# CellMonitor1.net
KiCad netlist of a schematic drawn in Altium Designer
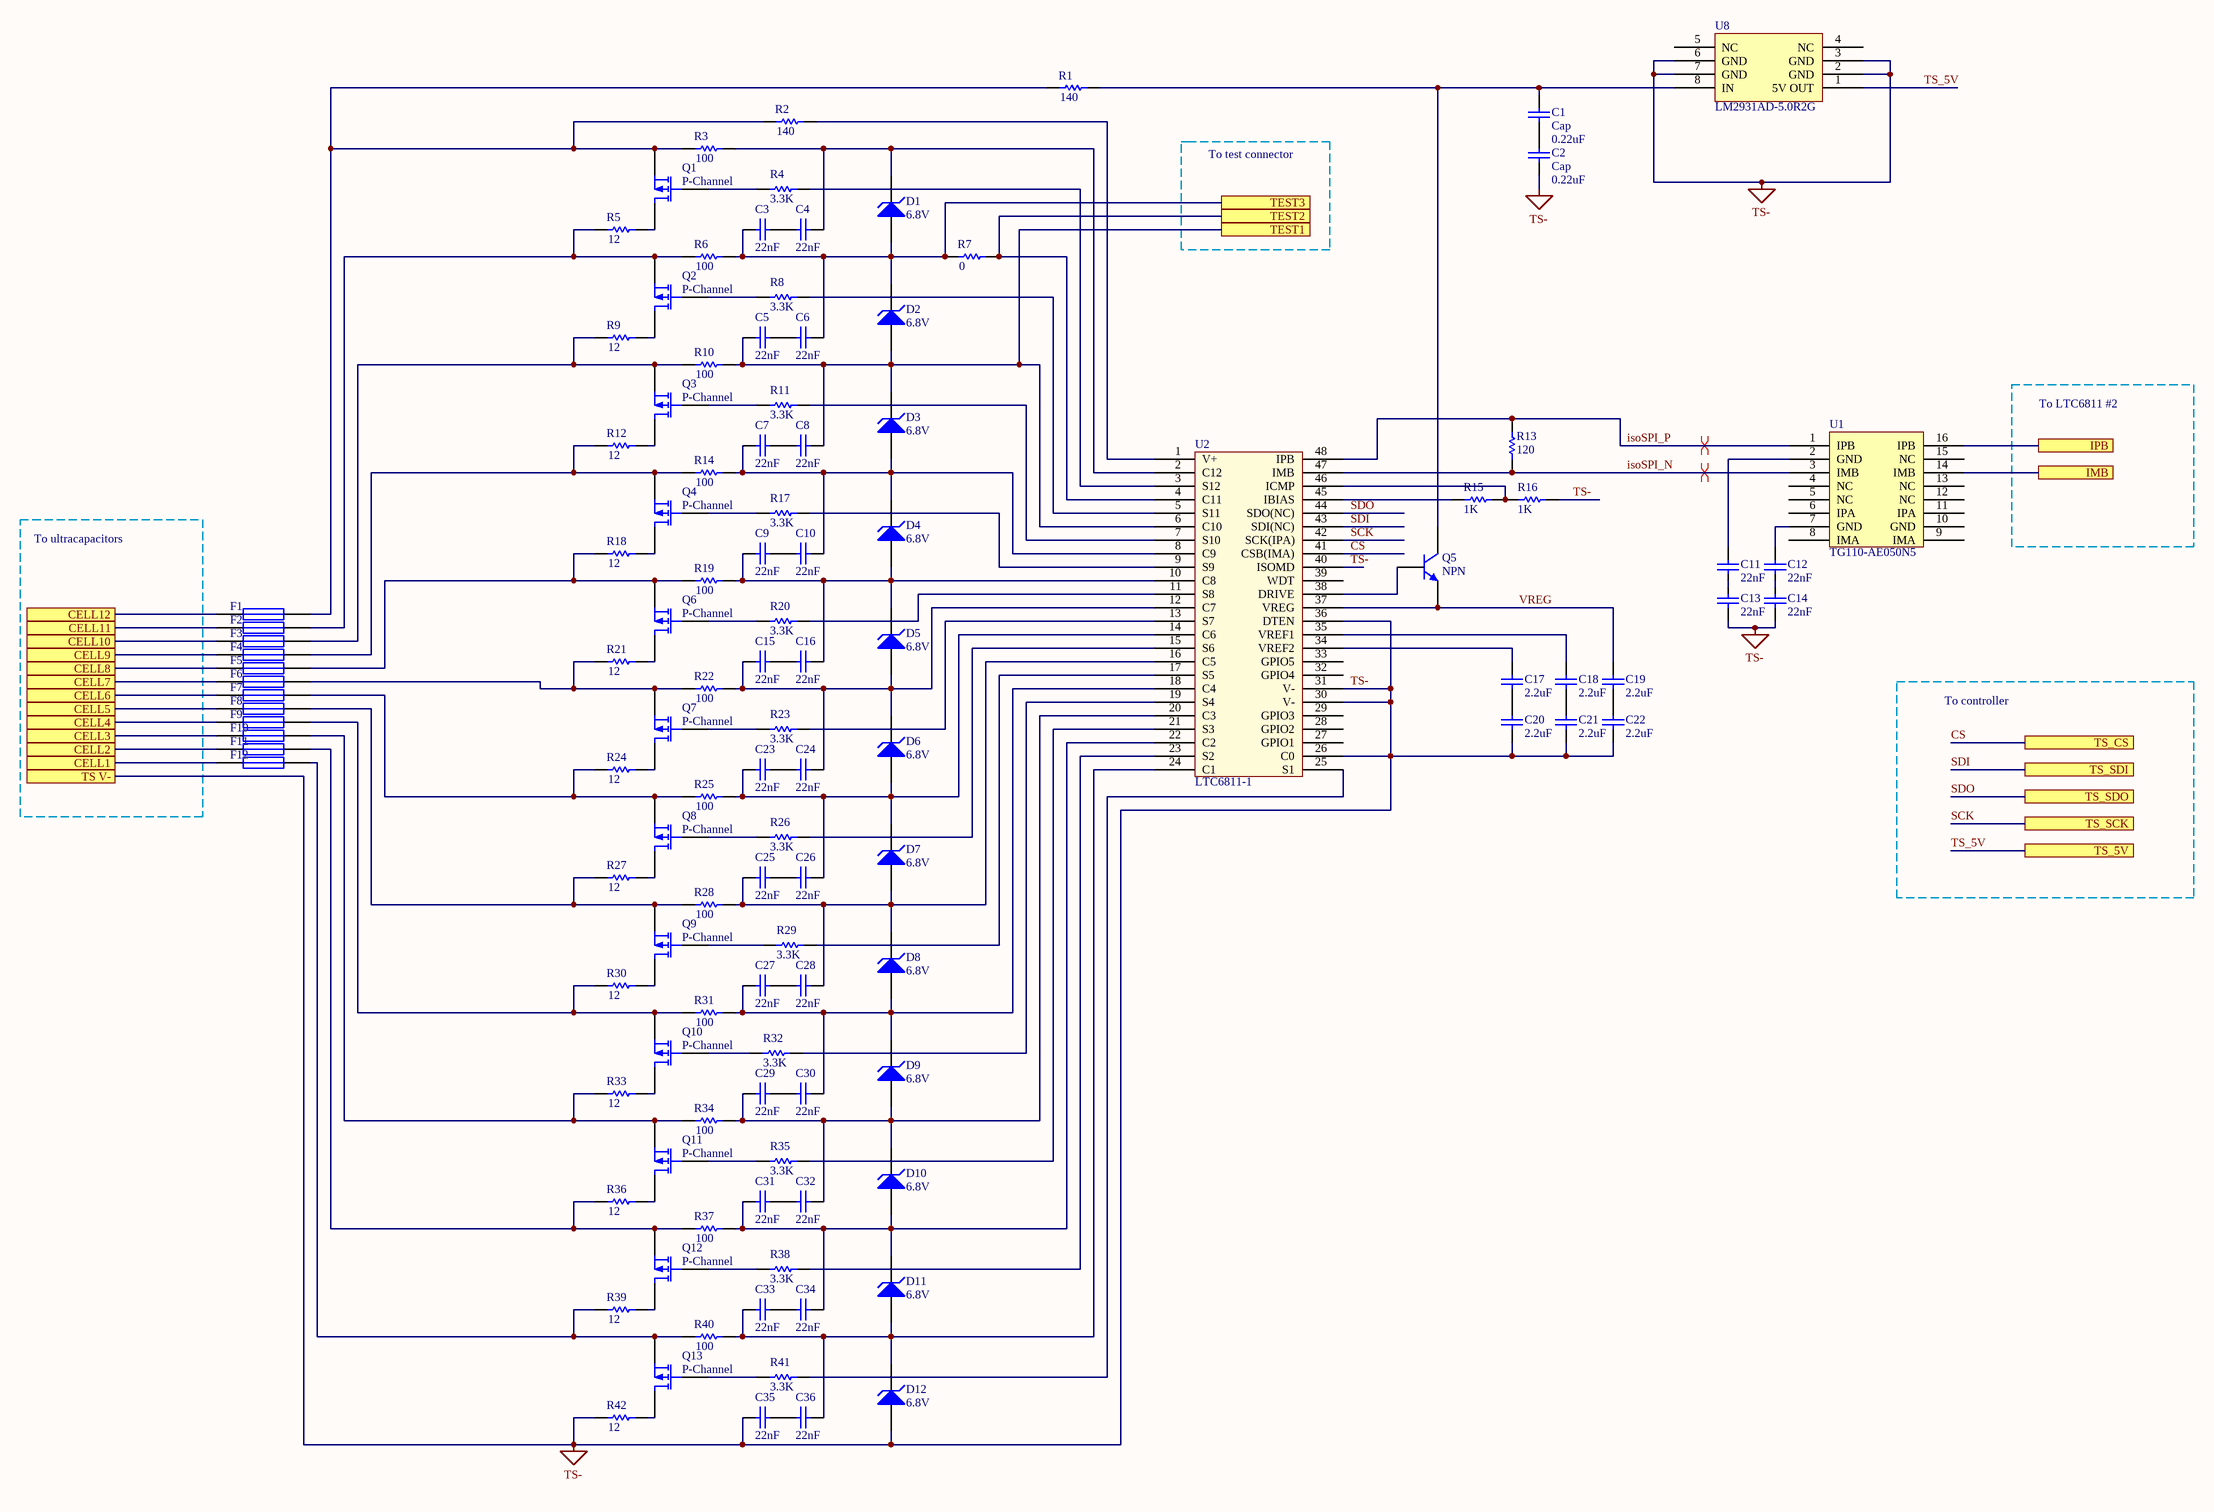
[diagram p0: CellMonitor1.SchDoc]

(export (version "E")
  (design (tool "Eeschema 10.0.6"))
  (components
    (comp (ref "C1")
      (value "Cap")
      (footprint "0603 IMPERIAL")
      (description "Capacitor")
      (fields (field (name "ALTIUM_VALUE") "0.22uF"))
      (libsource (lib "Miscellaneous Devices") (part "Cap"))
    )
    (comp (ref "C2")
      (value "Cap")
      (footprint "0603 IMPERIAL")
      (description "Capacitor")
      (fields (field (name "ALTIUM_VALUE") "0.22uF"))
      (libsource (lib "Miscellaneous Devices") (part "Cap"))
    )
    (comp (ref "C3")
      (value "22nF")
      (footprint "0603 IMPERIAL")
      (description "Capacitor")
      (fields (field (name "Comment") "Cap"))
      (libsource (lib "Miscellaneous Devices") (part "Cap"))
    )
    (comp (ref "C4")
      (value "22nF")
      (footprint "0603 IMPERIAL")
      (description "Capacitor")
      (fields (field (name "Comment") "Cap"))
      (libsource (lib "Miscellaneous Devices") (part "Cap"))
    )
    (comp (ref "C5")
      (value "22nF")
      (footprint "0603 IMPERIAL")
      (description "Capacitor")
      (fields (field (name "Comment") "Cap"))
      (libsource (lib "Miscellaneous Devices") (part "Cap"))
    )
    (comp (ref "C6")
      (value "22nF")
      (footprint "0603 IMPERIAL")
      (description "Capacitor")
      (fields (field (name "Comment") "Cap"))
      (libsource (lib "Miscellaneous Devices") (part "Cap"))
    )
    (comp (ref "C7")
      (value "22nF")
      (footprint "0603 IMPERIAL")
      (description "Capacitor")
      (fields (field (name "Comment") "Cap"))
      (libsource (lib "Miscellaneous Devices") (part "Cap"))
    )
    (comp (ref "C8")
      (value "22nF")
      (footprint "0603 IMPERIAL")
      (description "Capacitor")
      (fields (field (name "Comment") "Cap"))
      (libsource (lib "Miscellaneous Devices") (part "Cap"))
    )
    (comp (ref "C9")
      (value "22nF")
      (footprint "0603 IMPERIAL")
      (description "Capacitor")
      (fields (field (name "Comment") "Cap"))
      (libsource (lib "Miscellaneous Devices") (part "Cap"))
    )
    (comp (ref "C10")
      (value "22nF")
      (footprint "0603 IMPERIAL")
      (description "Capacitor")
      (fields (field (name "Comment") "Cap"))
      (libsource (lib "Miscellaneous Devices") (part "Cap"))
    )
    (comp (ref "C11")
      (value "22nF")
      (footprint "0603 IMPERIAL")
      (description "Capacitor")
      (fields (field (name "Comment") "Cap"))
      (libsource (lib "Miscellaneous Devices") (part "Cap"))
    )
    (comp (ref "C12")
      (value "22nF")
      (footprint "0603 IMPERIAL")
      (description "Capacitor")
      (fields (field (name "Comment") "Cap"))
      (libsource (lib "Miscellaneous Devices") (part "Cap"))
    )
    (comp (ref "C13")
      (value "22nF")
      (footprint "0603 IMPERIAL")
      (description "Capacitor")
      (fields (field (name "Comment") "Cap"))
      (libsource (lib "Miscellaneous Devices") (part "Cap"))
    )
    (comp (ref "C14")
      (value "22nF")
      (footprint "0603 IMPERIAL")
      (description "Capacitor")
      (fields (field (name "Comment") "Cap"))
      (libsource (lib "Miscellaneous Devices") (part "Cap"))
    )
    (comp (ref "C15")
      (value "22nF")
      (footprint "0603 IMPERIAL")
      (description "Capacitor")
      (fields (field (name "Comment") "Cap"))
      (libsource (lib "Miscellaneous Devices") (part "Cap"))
    )
    (comp (ref "C16")
      (value "22nF")
      (footprint "0603 IMPERIAL")
      (description "Capacitor")
      (fields (field (name "Comment") "Cap"))
      (libsource (lib "Miscellaneous Devices") (part "Cap"))
    )
    (comp (ref "C17")
      (value "2.2uF")
      (footprint "0603 IMPERIAL")
      (description "Capacitor")
      (fields (field (name "Comment") "Cap"))
      (libsource (lib "Miscellaneous Devices") (part "Cap"))
    )
    (comp (ref "C18")
      (value "2.2uF")
      (footprint "0603 IMPERIAL")
      (description "Capacitor")
      (fields (field (name "Comment") "Cap"))
      (libsource (lib "Miscellaneous Devices") (part "Cap"))
    )
    (comp (ref "C19")
      (value "2.2uF")
      (footprint "0603 IMPERIAL")
      (description "Capacitor")
      (fields (field (name "Comment") "Cap"))
      (libsource (lib "Miscellaneous Devices") (part "Cap"))
    )
    (comp (ref "C20")
      (value "2.2uF")
      (footprint "0603 IMPERIAL")
      (description "Capacitor")
      (fields (field (name "Comment") "Cap"))
      (libsource (lib "Miscellaneous Devices") (part "Cap"))
    )
    (comp (ref "C21")
      (value "2.2uF")
      (footprint "0603 IMPERIAL")
      (description "Capacitor")
      (fields (field (name "Comment") "Cap"))
      (libsource (lib "Miscellaneous Devices") (part "Cap"))
    )
    (comp (ref "C22")
      (value "2.2uF")
      (footprint "0603 IMPERIAL")
      (description "Capacitor")
      (fields (field (name "Comment") "Cap"))
      (libsource (lib "Miscellaneous Devices") (part "Cap"))
    )
    (comp (ref "C23")
      (value "22nF")
      (footprint "0603 IMPERIAL")
      (description "Capacitor")
      (fields (field (name "Comment") "Cap"))
      (libsource (lib "Miscellaneous Devices") (part "Cap"))
    )
    (comp (ref "C24")
      (value "22nF")
      (footprint "0603 IMPERIAL")
      (description "Capacitor")
      (fields (field (name "Comment") "Cap"))
      (libsource (lib "Miscellaneous Devices") (part "Cap"))
    )
    (comp (ref "C25")
      (value "22nF")
      (footprint "0603 IMPERIAL")
      (description "Capacitor")
      (fields (field (name "Comment") "Cap"))
      (libsource (lib "Miscellaneous Devices") (part "Cap"))
    )
    (comp (ref "C26")
      (value "22nF")
      (footprint "0603 IMPERIAL")
      (description "Capacitor")
      (fields (field (name "Comment") "Cap"))
      (libsource (lib "Miscellaneous Devices") (part "Cap"))
    )
    (comp (ref "C27")
      (value "22nF")
      (footprint "0603 IMPERIAL")
      (description "Capacitor")
      (fields (field (name "Comment") "Cap"))
      (libsource (lib "Miscellaneous Devices") (part "Cap"))
    )
    (comp (ref "C28")
      (value "22nF")
      (footprint "0603 IMPERIAL")
      (description "Capacitor")
      (fields (field (name "Comment") "Cap"))
      (libsource (lib "Miscellaneous Devices") (part "Cap"))
    )
    (comp (ref "C29")
      (value "22nF")
      (footprint "0603 IMPERIAL")
      (description "Capacitor")
      (fields (field (name "Comment") "Cap"))
      (libsource (lib "Miscellaneous Devices") (part "Cap"))
    )
    (comp (ref "C30")
      (value "22nF")
      (footprint "0603 IMPERIAL")
      (description "Capacitor")
      (fields (field (name "Comment") "Cap"))
      (libsource (lib "Miscellaneous Devices") (part "Cap"))
    )
    (comp (ref "C31")
      (value "22nF")
      (footprint "0603 IMPERIAL")
      (description "Capacitor")
      (fields (field (name "Comment") "Cap"))
      (libsource (lib "Miscellaneous Devices") (part "Cap"))
    )
    (comp (ref "C32")
      (value "22nF")
      (footprint "0603 IMPERIAL")
      (description "Capacitor")
      (fields (field (name "Comment") "Cap"))
      (libsource (lib "Miscellaneous Devices") (part "Cap"))
    )
    (comp (ref "C33")
      (value "22nF")
      (footprint "0603 IMPERIAL")
      (description "Capacitor")
      (fields (field (name "Comment") "Cap"))
      (libsource (lib "Miscellaneous Devices") (part "Cap"))
    )
    (comp (ref "C34")
      (value "22nF")
      (footprint "0603 IMPERIAL")
      (description "Capacitor")
      (fields (field (name "Comment") "Cap"))
      (libsource (lib "Miscellaneous Devices") (part "Cap"))
    )
    (comp (ref "C35")
      (value "22nF")
      (footprint "0603 IMPERIAL")
      (description "Capacitor")
      (fields (field (name "Comment") "Cap"))
      (libsource (lib "Miscellaneous Devices") (part "Cap"))
    )
    (comp (ref "C36")
      (value "22nF")
      (footprint "0603 IMPERIAL")
      (description "Capacitor")
      (fields (field (name "Comment") "Cap"))
      (libsource (lib "Miscellaneous Devices") (part "Cap"))
    )
    (comp (ref "D1")
      (value "6.8V")
      (footprint "SOD-323")
      (description "Zener Diode")
      (libsource (lib "Miscellaneous Devices") (part "D Zener"))
    )
    (comp (ref "D2")
      (value "6.8V")
      (footprint "SOD-323")
      (description "Zener Diode")
      (libsource (lib "Miscellaneous Devices") (part "D Zener"))
    )
    (comp (ref "D3")
      (value "6.8V")
      (footprint "SOD-323")
      (description "Zener Diode")
      (libsource (lib "Miscellaneous Devices") (part "D Zener"))
    )
    (comp (ref "D4")
      (value "6.8V")
      (footprint "SOD-323")
      (description "Zener Diode")
      (libsource (lib "Miscellaneous Devices") (part "D Zener"))
    )
    (comp (ref "D5")
      (value "6.8V")
      (footprint "SOD-323")
      (description "Zener Diode")
      (libsource (lib "Miscellaneous Devices") (part "D Zener"))
    )
    (comp (ref "D6")
      (value "6.8V")
      (footprint "SOD-323")
      (description "Zener Diode")
      (libsource (lib "Miscellaneous Devices") (part "D Zener"))
    )
    (comp (ref "D7")
      (value "6.8V")
      (footprint "SOD-323")
      (description "Zener Diode")
      (libsource (lib "Miscellaneous Devices") (part "D Zener"))
    )
    (comp (ref "D8")
      (value "6.8V")
      (footprint "SOD-323")
      (description "Zener Diode")
      (libsource (lib "Miscellaneous Devices") (part "D Zener"))
    )
    (comp (ref "D9")
      (value "6.8V")
      (footprint "SOD-323")
      (description "Zener Diode")
      (libsource (lib "Miscellaneous Devices") (part "D Zener"))
    )
    (comp (ref "D10")
      (value "6.8V")
      (footprint "SOD-323")
      (description "Zener Diode")
      (libsource (lib "Miscellaneous Devices") (part "D Zener"))
    )
    (comp (ref "D11")
      (value "6.8V")
      (footprint "SOD-323")
      (description "Zener Diode")
      (libsource (lib "Miscellaneous Devices") (part "D Zener"))
    )
    (comp (ref "D12")
      (value "6.8V")
      (footprint "SOD-323")
      (description "Zener Diode")
      (libsource (lib "Miscellaneous Devices") (part "D Zener"))
    )
    (comp (ref "F1")
      (value "0451.500NRL")
      (footprint "0451.500NRL")
      (description "Fuse")
      (libsource (lib "Miscellaneous Devices") (part "Fuse 1"))
    )
    (comp (ref "F2")
      (value "0451.500NRL")
      (footprint "0451.500NRL")
      (description "Fuse")
      (libsource (lib "Miscellaneous Devices") (part "Fuse 1"))
    )
    (comp (ref "F3")
      (value "0451.500NRL")
      (footprint "0451.500NRL")
      (description "Fuse")
      (libsource (lib "Miscellaneous Devices") (part "Fuse 1"))
    )
    (comp (ref "F4")
      (value "0451.500NRL")
      (footprint "0451.500NRL")
      (description "Fuse")
      (libsource (lib "Miscellaneous Devices") (part "Fuse 1"))
    )
    (comp (ref "F5")
      (value "0451.500NRL")
      (footprint "0451.500NRL")
      (description "Fuse")
      (libsource (lib "Miscellaneous Devices") (part "Fuse 1"))
    )
    (comp (ref "F6")
      (value "0451.500NRL")
      (footprint "0451.500NRL")
      (description "Fuse")
      (libsource (lib "Miscellaneous Devices") (part "Fuse 1"))
    )
    (comp (ref "F7")
      (value "0451.500NRL")
      (footprint "0451.500NRL")
      (description "Fuse")
      (libsource (lib "Miscellaneous Devices") (part "Fuse 1"))
    )
    (comp (ref "F8")
      (value "0451.500NRL")
      (footprint "0451.500NRL")
      (description "Fuse")
      (libsource (lib "Miscellaneous Devices") (part "Fuse 1"))
    )
    (comp (ref "F9")
      (value "0451.500NRL")
      (footprint "0451.500NRL")
      (description "Fuse")
      (libsource (lib "Miscellaneous Devices") (part "Fuse 1"))
    )
    (comp (ref "F10")
      (value "0451.500NRL")
      (footprint "0451.500NRL")
      (description "Fuse")
      (libsource (lib "Miscellaneous Devices") (part "Fuse 1"))
    )
    (comp (ref "F11")
      (value "0451.500NRL")
      (footprint "0451.500NRL")
      (description "Fuse")
      (libsource (lib "Miscellaneous Devices") (part "Fuse 1"))
    )
    (comp (ref "F12")
      (value "0451.500NRL")
      (footprint "0451.500NRL")
      (description "Fuse")
      (libsource (lib "Miscellaneous Devices") (part "Fuse 1"))
    )
    (comp (ref "Q1")
      (value "P-Channel")
      (footprint "SOT23F")
      (description "P-Channel MOSFET")
      (libsource (lib "Miscellaneous Devices") (part "MOSFET-P"))
    )
    (comp (ref "Q2")
      (value "P-Channel")
      (footprint "SOT23F")
      (description "P-Channel MOSFET")
      (libsource (lib "Miscellaneous Devices") (part "MOSFET-P"))
    )
    (comp (ref "Q3")
      (value "P-Channel")
      (footprint "SOT23F")
      (description "P-Channel MOSFET")
      (libsource (lib "Miscellaneous Devices") (part "MOSFET-P"))
    )
    (comp (ref "Q4")
      (value "P-Channel")
      (footprint "SOT23F")
      (description "P-Channel MOSFET")
      (libsource (lib "Miscellaneous Devices") (part "MOSFET-P"))
    )
    (comp (ref "Q5")
      (value "NPN")
      (footprint "SOT223_N")
      (description "NPN General Purpose Amplifier")
      (libsource (lib "Miscellaneous Devices") (part "2N3904"))
    )
    (comp (ref "Q6")
      (value "P-Channel")
      (footprint "SOT23F")
      (description "P-Channel MOSFET")
      (libsource (lib "Miscellaneous Devices") (part "MOSFET-P"))
    )
    (comp (ref "Q7")
      (value "P-Channel")
      (footprint "SOT23F")
      (description "P-Channel MOSFET")
      (libsource (lib "Miscellaneous Devices") (part "MOSFET-P"))
    )
    (comp (ref "Q8")
      (value "P-Channel")
      (footprint "SOT23F")
      (description "P-Channel MOSFET")
      (libsource (lib "Miscellaneous Devices") (part "MOSFET-P"))
    )
    (comp (ref "Q9")
      (value "P-Channel")
      (footprint "SOT23F")
      (description "P-Channel MOSFET")
      (libsource (lib "Miscellaneous Devices") (part "MOSFET-P"))
    )
    (comp (ref "Q10")
      (value "P-Channel")
      (footprint "SOT23F")
      (description "P-Channel MOSFET")
      (libsource (lib "Miscellaneous Devices") (part "MOSFET-P"))
    )
    (comp (ref "Q11")
      (value "P-Channel")
      (footprint "SOT23F")
      (description "P-Channel MOSFET")
      (libsource (lib "Miscellaneous Devices") (part "MOSFET-P"))
    )
    (comp (ref "Q12")
      (value "P-Channel")
      (footprint "SOT23F")
      (description "P-Channel MOSFET")
      (libsource (lib "Miscellaneous Devices") (part "MOSFET-P"))
    )
    (comp (ref "Q13")
      (value "P-Channel")
      (footprint "SOT23F")
      (description "P-Channel MOSFET")
      (libsource (lib "Miscellaneous Devices") (part "MOSFET-P"))
    )
    (comp (ref "R1")
      (value "140")
      (footprint "0603 IMPERIAL")
      (description "Resistor")
      (fields (field (name "Comment") "Res1"))
      (libsource (lib "Miscellaneous Devices") (part "Res1"))
    )
    (comp (ref "R2")
      (value "140")
      (footprint "0603 IMPERIAL")
      (description "Resistor")
      (fields (field (name "Comment") "Res1"))
      (libsource (lib "Miscellaneous Devices") (part "Res1"))
    )
    (comp (ref "R3")
      (value "100")
      (footprint "0603 IMPERIAL")
      (description "Resistor")
      (fields (field (name "Comment") "Res1"))
      (libsource (lib "Miscellaneous Devices") (part "Res1"))
    )
    (comp (ref "R4")
      (value "3.3K")
      (footprint "0603 IMPERIAL")
      (description "Resistor")
      (fields (field (name "Comment") "Res1"))
      (libsource (lib "Miscellaneous Devices") (part "Res1"))
    )
    (comp (ref "R5")
      (value "12")
      (footprint "2512 IMPERIAL")
      (description "Resistor")
      (fields (field (name "Comment") "Res1"))
      (libsource (lib "Miscellaneous Devices") (part "Res1"))
    )
    (comp (ref "R6")
      (value "100")
      (footprint "0603 IMPERIAL")
      (description "Resistor")
      (fields (field (name "Comment") "Res1"))
      (libsource (lib "Miscellaneous Devices") (part "Res1"))
    )
    (comp (ref "R7")
      (value "0")
      (footprint "0603 IMPERIAL")
      (description "Resistor")
      (fields (field (name "Comment") "Res1"))
      (libsource (lib "Miscellaneous Devices") (part "Res1"))
    )
    (comp (ref "R8")
      (value "3.3K")
      (footprint "0603 IMPERIAL")
      (description "Resistor")
      (fields (field (name "Comment") "Res1"))
      (libsource (lib "Miscellaneous Devices") (part "Res1"))
    )
    (comp (ref "R9")
      (value "12")
      (footprint "2512 IMPERIAL")
      (description "Resistor")
      (fields (field (name "Comment") "Res1"))
      (libsource (lib "Miscellaneous Devices") (part "Res1"))
    )
    (comp (ref "R10")
      (value "100")
      (footprint "0603 IMPERIAL")
      (description "Resistor")
      (fields (field (name "Comment") "Res1"))
      (libsource (lib "Miscellaneous Devices") (part "Res1"))
    )
    (comp (ref "R11")
      (value "3.3K")
      (footprint "0603 IMPERIAL")
      (description "Resistor")
      (fields (field (name "Comment") "Res1"))
      (libsource (lib "Miscellaneous Devices") (part "Res1"))
    )
    (comp (ref "R12")
      (value "12")
      (footprint "2512 IMPERIAL")
      (description "Resistor")
      (fields (field (name "Comment") "Res1"))
      (libsource (lib "Miscellaneous Devices") (part "Res1"))
    )
    (comp (ref "R13")
      (value "120")
      (footprint "0603 IMPERIAL")
      (description "Resistor")
      (libsource (lib "Miscellaneous Devices") (part "Res1"))
    )
    (comp (ref "R14")
      (value "100")
      (footprint "0603 IMPERIAL")
      (description "Resistor")
      (fields (field (name "Comment") "Res1"))
      (libsource (lib "Miscellaneous Devices") (part "Res1"))
    )
    (comp (ref "R15")
      (value "1K")
      (footprint "0603 IMPERIAL")
      (description "Resistor")
      (libsource (lib "Miscellaneous Devices") (part "Res1"))
    )
    (comp (ref "R16")
      (value "1K")
      (footprint "0603 IMPERIAL")
      (description "Resistor")
      (libsource (lib "Miscellaneous Devices") (part "Res1"))
    )
    (comp (ref "R17")
      (value "3.3K")
      (footprint "0603 IMPERIAL")
      (description "Resistor")
      (fields (field (name "Comment") "Res1"))
      (libsource (lib "Miscellaneous Devices") (part "Res1"))
    )
    (comp (ref "R18")
      (value "12")
      (footprint "2512 IMPERIAL")
      (description "Resistor")
      (fields (field (name "Comment") "Res1"))
      (libsource (lib "Miscellaneous Devices") (part "Res1"))
    )
    (comp (ref "R19")
      (value "100")
      (footprint "0603 IMPERIAL")
      (description "Resistor")
      (fields (field (name "Comment") "Res1"))
      (libsource (lib "Miscellaneous Devices") (part "Res1"))
    )
    (comp (ref "R20")
      (value "3.3K")
      (footprint "0603 IMPERIAL")
      (description "Resistor")
      (fields (field (name "Comment") "Res1"))
      (libsource (lib "Miscellaneous Devices") (part "Res1"))
    )
    (comp (ref "R21")
      (value "12")
      (footprint "2512 IMPERIAL")
      (description "Resistor")
      (fields (field (name "Comment") "Res1"))
      (libsource (lib "Miscellaneous Devices") (part "Res1"))
    )
    (comp (ref "R22")
      (value "100")
      (footprint "0603 IMPERIAL")
      (description "Resistor")
      (fields (field (name "Comment") "Res1"))
      (libsource (lib "Miscellaneous Devices") (part "Res1"))
    )
    (comp (ref "R23")
      (value "3.3K")
      (footprint "0603 IMPERIAL")
      (description "Resistor")
      (fields (field (name "Comment") "Res1"))
      (libsource (lib "Miscellaneous Devices") (part "Res1"))
    )
    (comp (ref "R24")
      (value "12")
      (footprint "2512 IMPERIAL")
      (description "Resistor")
      (fields (field (name "Comment") "Res1"))
      (libsource (lib "Miscellaneous Devices") (part "Res1"))
    )
    (comp (ref "R25")
      (value "100")
      (footprint "0603 IMPERIAL")
      (description "Resistor")
      (fields (field (name "Comment") "Res1"))
      (libsource (lib "Miscellaneous Devices") (part "Res1"))
    )
    (comp (ref "R26")
      (value "3.3K")
      (footprint "0603 IMPERIAL")
      (description "Resistor")
      (fields (field (name "Comment") "Res1"))
      (libsource (lib "Miscellaneous Devices") (part "Res1"))
    )
    (comp (ref "R27")
      (value "12")
      (footprint "2512 IMPERIAL")
      (description "Resistor")
      (fields (field (name "Comment") "Res1"))
      (libsource (lib "Miscellaneous Devices") (part "Res1"))
    )
    (comp (ref "R28")
      (value "100")
      (footprint "0603 IMPERIAL")
      (description "Resistor")
      (fields (field (name "Comment") "Res1"))
      (libsource (lib "Miscellaneous Devices") (part "Res1"))
    )
    (comp (ref "R29")
      (value "3.3K")
      (footprint "0603 IMPERIAL")
      (description "Resistor")
      (fields (field (name "Comment") "Res1"))
      (libsource (lib "Miscellaneous Devices") (part "Res1"))
    )
    (comp (ref "R30")
      (value "12")
      (footprint "2512 IMPERIAL")
      (description "Resistor")
      (fields (field (name "Comment") "Res1"))
      (libsource (lib "Miscellaneous Devices") (part "Res1"))
    )
    (comp (ref "R31")
      (value "100")
      (footprint "0603 IMPERIAL")
      (description "Resistor")
      (fields (field (name "Comment") "Res1"))
      (libsource (lib "Miscellaneous Devices") (part "Res1"))
    )
    (comp (ref "R32")
      (value "3.3K")
      (footprint "0603 IMPERIAL")
      (description "Resistor")
      (fields (field (name "Comment") "Res1"))
      (libsource (lib "Miscellaneous Devices") (part "Res1"))
    )
    (comp (ref "R33")
      (value "12")
      (footprint "2512 IMPERIAL")
      (description "Resistor")
      (fields (field (name "Comment") "Res1"))
      (libsource (lib "Miscellaneous Devices") (part "Res1"))
    )
    (comp (ref "R34")
      (value "100")
      (footprint "0603 IMPERIAL")
      (description "Resistor")
      (fields (field (name "Comment") "Res1"))
      (libsource (lib "Miscellaneous Devices") (part "Res1"))
    )
    (comp (ref "R35")
      (value "3.3K")
      (footprint "0603 IMPERIAL")
      (description "Resistor")
      (fields (field (name "Comment") "Res1"))
      (libsource (lib "Miscellaneous Devices") (part "Res1"))
    )
    (comp (ref "R36")
      (value "12")
      (footprint "2512 IMPERIAL")
      (description "Resistor")
      (fields (field (name "Comment") "Res1"))
      (libsource (lib "Miscellaneous Devices") (part "Res1"))
    )
    (comp (ref "R37")
      (value "100")
      (footprint "0603 IMPERIAL")
      (description "Resistor")
      (fields (field (name "Comment") "Res1"))
      (libsource (lib "Miscellaneous Devices") (part "Res1"))
    )
    (comp (ref "R38")
      (value "3.3K")
      (footprint "0603 IMPERIAL")
      (description "Resistor")
      (fields (field (name "Comment") "Res1"))
      (libsource (lib "Miscellaneous Devices") (part "Res1"))
    )
    (comp (ref "R39")
      (value "12")
      (footprint "2512 IMPERIAL")
      (description "Resistor")
      (fields (field (name "Comment") "Res1"))
      (libsource (lib "Miscellaneous Devices") (part "Res1"))
    )
    (comp (ref "R40")
      (value "100")
      (footprint "0603 IMPERIAL")
      (description "Resistor")
      (fields (field (name "Comment") "Res1"))
      (libsource (lib "Miscellaneous Devices") (part "Res1"))
    )
    (comp (ref "R41")
      (value "3.3K")
      (footprint "0603 IMPERIAL")
      (description "Resistor")
      (fields (field (name "Comment") "Res1"))
      (libsource (lib "Miscellaneous Devices") (part "Res1"))
    )
    (comp (ref "R42")
      (value "12")
      (footprint "2512 IMPERIAL")
      (description "Resistor")
      (fields (field (name "Comment") "Res1"))
      (libsource (lib "Miscellaneous Devices") (part "Res1"))
    )
    (comp (ref "U1")
      (value "TG110-AE050N5")
      (footprint "Halo N5")
      (libsource (lib "UVICHybridLibrary") (part "TG110-AE050N5"))
    )
    (comp (ref "U2")
      (value "LTC6811-1")
      (footprint "SSOP-48")
      (libsource (lib "UVICHybridLibrary") (part "LTC6811-1"))
    )
    (comp (ref "U8")
      (value "LM2931AD-5.0R2G")
      (footprint "8-SOIC")
      (description "IC REG LINEAR 5V 100MA 8SOIC")
      (libsource (lib "AMSComponents") (part "LM2931AD-5.0R2G"))
    )
  )
  (nets
    (net (code "1") (name "/CELL1") (class "Default")
      (node (ref "F12") (pin "1") (pinfunction "1_1") (pintype "passive"))
    )
    (net (code "2") (name "/CELL2") (class "Default")
      (node (ref "F11") (pin "1") (pinfunction "1_1") (pintype "passive"))
    )
    (net (code "3") (name "/CELL3") (class "Default")
      (node (ref "F10") (pin "1") (pinfunction "1_1") (pintype "passive"))
    )
    (net (code "4") (name "/CELL4") (class "Default")
      (node (ref "F9") (pin "1") (pinfunction "1_1") (pintype "passive"))
    )
    (net (code "5") (name "/CELL5") (class "Default")
      (node (ref "F8") (pin "1") (pinfunction "1_1") (pintype "passive"))
    )
    (net (code "6") (name "/CELL6") (class "Default")
      (node (ref "F7") (pin "1") (pinfunction "1_1") (pintype "passive"))
    )
    (net (code "7") (name "/CELL7") (class "Default")
      (node (ref "F6") (pin "1") (pinfunction "1_1") (pintype "passive"))
    )
    (net (code "8") (name "/CELL8") (class "Default")
      (node (ref "F5") (pin "1") (pinfunction "1_1") (pintype "passive"))
    )
    (net (code "9") (name "/CELL9") (class "Default")
      (node (ref "F4") (pin "1") (pinfunction "1_1") (pintype "passive"))
    )
    (net (code "10") (name "/CELL10") (class "Default")
      (node (ref "F3") (pin "1") (pinfunction "1_1") (pintype "passive"))
    )
    (net (code "11") (name "/CELL11") (class "Default")
      (node (ref "F2") (pin "1") (pinfunction "1_1") (pintype "passive"))
    )
    (net (code "12") (name "/CELL12") (class "Default")
      (node (ref "F1") (pin "1") (pinfunction "1_1") (pintype "passive"))
    )
    (net (code "13") (name "/CS") (class "Default")
      (node (ref "U2") (pin "41") (pinfunction "CSB(IMA)_41") (pintype "passive"))
    )
    (net (code "14") (name "/IMB") (class "Default")
      (node (ref "U1") (pin "14") (pinfunction "IMB_14") (pintype "passive"))
    )
    (net (code "15") (name "/IPB") (class "Default")
      (node (ref "U1") (pin "16") (pinfunction "IPB_16") (pintype "passive"))
    )
    (net (code "16") (name "/SCK") (class "Default")
      (node (ref "U2") (pin "42") (pinfunction "SCK(IPA)_42") (pintype "passive"))
    )
    (net (code "17") (name "/SDI") (class "Default")
      (node (ref "U2") (pin "43") (pinfunction "SDI(NC)_43") (pintype "passive"))
    )
    (net (code "18") (name "/SDO") (class "Default")
      (node (ref "U2") (pin "44") (pinfunction "SDO(NC)_44") (pintype "passive"))
    )
    (net (code "19") (name "/TEST1") (class "Default")
      (node (ref "C5") (pin "2") (pinfunction "2_2") (pintype "passive"))
      (node (ref "C8") (pin "1") (pinfunction "1_1") (pintype "passive"))
      (node (ref "D2") (pin "1") (pinfunction "A_1") (pintype "passive"))
      (node (ref "D3") (pin "2") (pinfunction "K_2") (pintype "passive"))
      (node (ref "R10") (pin "2") (pinfunction "2_2") (pintype "passive"))
      (node (ref "U2") (pin "6") (pinfunction "C10_6") (pintype "passive"))
    )
    (net (code "20") (name "/TEST2") (class "Default")
      (node (ref "R7") (pin "2") (pinfunction "2_2") (pintype "passive"))
      (node (ref "U2") (pin "4") (pinfunction "C11_4") (pintype "passive"))
    )
    (net (code "21") (name "/TEST3") (class "Default")
      (node (ref "C3") (pin "2") (pinfunction "2_2") (pintype "passive"))
      (node (ref "C6") (pin "1") (pinfunction "1_1") (pintype "passive"))
      (node (ref "D1") (pin "1") (pinfunction "A_1") (pintype "passive"))
      (node (ref "D2") (pin "2") (pinfunction "K_2") (pintype "passive"))
      (node (ref "R6") (pin "2") (pinfunction "2_2") (pintype "passive"))
      (node (ref "R7") (pin "1") (pinfunction "1_1") (pintype "passive"))
    )
    (net (code "22") (name "/TS_5V") (class "Default")
      (node (ref "U8") (pin "1") (pinfunction "5V_OUT_1") (pintype "passive"))
    )
    (net (code "23") (name "/VREG") (class "Default")
      (node (ref "C19") (pin "1") (pinfunction "1_1") (pintype "passive"))
      (node (ref "Q5") (pin "3") (pinfunction "E_3") (pintype "passive"))
      (node (ref "U2") (pin "37") (pinfunction "VREG_37") (pintype "passive"))
    )
    (net (code "24") (name "/isoSPI_N") (class "Default")
      (node (ref "R13") (pin "1") (pinfunction "1_1") (pintype "passive"))
      (node (ref "U1") (pin "3") (pinfunction "IMB_3") (pintype "passive"))
      (node (ref "U2") (pin "47") (pinfunction "IMB_47") (pintype "passive"))
    )
    (net (code "25") (name "/isoSPI_P") (class "Default")
      (node (ref "R13") (pin "2") (pinfunction "2_2") (pintype "passive"))
      (node (ref "U1") (pin "1") (pinfunction "IPB_1") (pintype "passive"))
      (node (ref "U2") (pin "48") (pinfunction "IPB_48") (pintype "passive"))
    )
    (net (code "26") (name "Net-(C1-Pad2)") (class "Default")
      (node (ref "C1") (pin "2") (pinfunction "2_2") (pintype "passive"))
      (node (ref "C2") (pin "1") (pinfunction "1_1") (pintype "passive"))
    )
    (net (code "27") (name "Net-(C3-Pad1)") (class "Default")
      (node (ref "C3") (pin "1") (pinfunction "1_1") (pintype "passive"))
      (node (ref "C4") (pin "2") (pinfunction "2_2") (pintype "passive"))
    )
    (net (code "28") (name "Net-(C5-Pad1)") (class "Default")
      (node (ref "C5") (pin "1") (pinfunction "1_1") (pintype "passive"))
      (node (ref "C6") (pin "2") (pinfunction "2_2") (pintype "passive"))
    )
    (net (code "29") (name "Net-(C7-Pad1)") (class "Default")
      (node (ref "C7") (pin "1") (pinfunction "1_1") (pintype "passive"))
      (node (ref "C8") (pin "2") (pinfunction "2_2") (pintype "passive"))
    )
    (net (code "30") (name "Net-(C10-Pad2)") (class "Default")
      (node (ref "C10") (pin "2") (pinfunction "2_2") (pintype "passive"))
      (node (ref "C9") (pin "1") (pinfunction "1_1") (pintype "passive"))
    )
    (net (code "31") (name "Net-(C11-Pad1)") (class "Default")
      (node (ref "C11") (pin "1") (pinfunction "1_1") (pintype "passive"))
      (node (ref "U1") (pin "2") (pinfunction "GND_2") (pintype "passive"))
    )
    (net (code "32") (name "Net-(C11-Pad2)") (class "Default")
      (node (ref "C11") (pin "2") (pinfunction "2_2") (pintype "passive"))
      (node (ref "C13") (pin "1") (pinfunction "1_1") (pintype "passive"))
    )
    (net (code "33") (name "Net-(C12-Pad1)") (class "Default")
      (node (ref "C12") (pin "1") (pinfunction "1_1") (pintype "passive"))
      (node (ref "U1") (pin "7") (pinfunction "GND_7") (pintype "passive"))
    )
    (net (code "34") (name "Net-(C12-Pad2)") (class "Default")
      (node (ref "C12") (pin "2") (pinfunction "2_2") (pintype "passive"))
      (node (ref "C14") (pin "1") (pinfunction "1_1") (pintype "passive"))
    )
    (net (code "35") (name "Net-(C15-Pad1)") (class "Default")
      (node (ref "C15") (pin "1") (pinfunction "1_1") (pintype "passive"))
      (node (ref "C16") (pin "2") (pinfunction "2_2") (pintype "passive"))
    )
    (net (code "36") (name "Net-(C17-Pad2)") (class "Default")
      (node (ref "C17") (pin "2") (pinfunction "2_2") (pintype "passive"))
      (node (ref "C20") (pin "1") (pinfunction "1_1") (pintype "passive"))
    )
    (net (code "37") (name "Net-(C18-Pad2)") (class "Default")
      (node (ref "C18") (pin "2") (pinfunction "2_2") (pintype "passive"))
      (node (ref "C21") (pin "1") (pinfunction "1_1") (pintype "passive"))
    )
    (net (code "38") (name "Net-(C19-Pad2)") (class "Default")
      (node (ref "C19") (pin "2") (pinfunction "2_2") (pintype "passive"))
      (node (ref "C22") (pin "1") (pinfunction "1_1") (pintype "passive"))
    )
    (net (code "39") (name "Net-(C23-Pad1)") (class "Default")
      (node (ref "C23") (pin "1") (pinfunction "1_1") (pintype "passive"))
      (node (ref "C24") (pin "2") (pinfunction "2_2") (pintype "passive"))
    )
    (net (code "40") (name "Net-(C25-Pad1)") (class "Default")
      (node (ref "C25") (pin "1") (pinfunction "1_1") (pintype "passive"))
      (node (ref "C26") (pin "2") (pinfunction "2_2") (pintype "passive"))
    )
    (net (code "41") (name "Net-(C27-Pad1)") (class "Default")
      (node (ref "C27") (pin "1") (pinfunction "1_1") (pintype "passive"))
      (node (ref "C28") (pin "2") (pinfunction "2_2") (pintype "passive"))
    )
    (net (code "42") (name "Net-(C29-Pad1)") (class "Default")
      (node (ref "C29") (pin "1") (pinfunction "1_1") (pintype "passive"))
      (node (ref "C30") (pin "2") (pinfunction "2_2") (pintype "passive"))
    )
    (net (code "43") (name "Net-(C31-Pad1)") (class "Default")
      (node (ref "C31") (pin "1") (pinfunction "1_1") (pintype "passive"))
      (node (ref "C32") (pin "2") (pinfunction "2_2") (pintype "passive"))
    )
    (net (code "44") (name "Net-(C33-Pad1)") (class "Default")
      (node (ref "C33") (pin "1") (pinfunction "1_1") (pintype "passive"))
      (node (ref "C34") (pin "2") (pinfunction "2_2") (pintype "passive"))
    )
    (net (code "45") (name "Net-(C35-Pad1)") (class "Default")
      (node (ref "C35") (pin "1") (pinfunction "1_1") (pintype "passive"))
      (node (ref "C36") (pin "2") (pinfunction "2_2") (pintype "passive"))
    )
    (net (code "46") (name "Net-(D1-K)") (class "Default")
      (node (ref "C4") (pin "1") (pinfunction "1_1") (pintype "passive"))
      (node (ref "D1") (pin "2") (pinfunction "K_2") (pintype "passive"))
      (node (ref "R3") (pin "2") (pinfunction "2_2") (pintype "passive"))
      (node (ref "U2") (pin "2") (pinfunction "C12_2") (pintype "passive"))
    )
    (net (code "47") (name "Net-(D3-A)") (class "Default")
      (node (ref "C10") (pin "1") (pinfunction "1_1") (pintype "passive"))
      (node (ref "C7") (pin "2") (pinfunction "2_2") (pintype "passive"))
      (node (ref "D3") (pin "1") (pinfunction "A_1") (pintype "passive"))
      (node (ref "D4") (pin "2") (pinfunction "K_2") (pintype "passive"))
      (node (ref "R14") (pin "2") (pinfunction "2_2") (pintype "passive"))
      (node (ref "U2") (pin "8") (pinfunction "C9_8") (pintype "passive"))
    )
    (net (code "48") (name "Net-(D4-A)") (class "Default")
      (node (ref "C16") (pin "1") (pinfunction "1_1") (pintype "passive"))
      (node (ref "C9") (pin "2") (pinfunction "2_2") (pintype "passive"))
      (node (ref "D4") (pin "1") (pinfunction "A_1") (pintype "passive"))
      (node (ref "D5") (pin "2") (pinfunction "K_2") (pintype "passive"))
      (node (ref "R19") (pin "2") (pinfunction "2_2") (pintype "passive"))
      (node (ref "U2") (pin "10") (pinfunction "C8_10") (pintype "passive"))
    )
    (net (code "49") (name "Net-(D5-A)") (class "Default")
      (node (ref "C15") (pin "2") (pinfunction "2_2") (pintype "passive"))
      (node (ref "C24") (pin "1") (pinfunction "1_1") (pintype "passive"))
      (node (ref "D5") (pin "1") (pinfunction "A_1") (pintype "passive"))
      (node (ref "D6") (pin "2") (pinfunction "K_2") (pintype "passive"))
      (node (ref "R22") (pin "2") (pinfunction "2_2") (pintype "passive"))
      (node (ref "U2") (pin "12") (pinfunction "C7_12") (pintype "passive"))
    )
    (net (code "50") (name "Net-(D6-A)") (class "Default")
      (node (ref "C23") (pin "2") (pinfunction "2_2") (pintype "passive"))
      (node (ref "C26") (pin "1") (pinfunction "1_1") (pintype "passive"))
      (node (ref "D6") (pin "1") (pinfunction "A_1") (pintype "passive"))
      (node (ref "D7") (pin "2") (pinfunction "K_2") (pintype "passive"))
      (node (ref "R25") (pin "2") (pinfunction "2_2") (pintype "passive"))
      (node (ref "U2") (pin "14") (pinfunction "C6_14") (pintype "passive"))
    )
    (net (code "51") (name "Net-(D7-A)") (class "Default")
      (node (ref "C25") (pin "2") (pinfunction "2_2") (pintype "passive"))
      (node (ref "C28") (pin "1") (pinfunction "1_1") (pintype "passive"))
      (node (ref "D7") (pin "1") (pinfunction "A_1") (pintype "passive"))
      (node (ref "D8") (pin "2") (pinfunction "K_2") (pintype "passive"))
      (node (ref "R28") (pin "2") (pinfunction "2_2") (pintype "passive"))
      (node (ref "U2") (pin "16") (pinfunction "C5_16") (pintype "passive"))
    )
    (net (code "52") (name "Net-(D8-A)") (class "Default")
      (node (ref "C27") (pin "2") (pinfunction "2_2") (pintype "passive"))
      (node (ref "C30") (pin "1") (pinfunction "1_1") (pintype "passive"))
      (node (ref "D8") (pin "1") (pinfunction "A_1") (pintype "passive"))
      (node (ref "D9") (pin "2") (pinfunction "K_2") (pintype "passive"))
      (node (ref "R31") (pin "2") (pinfunction "2_2") (pintype "passive"))
      (node (ref "U2") (pin "18") (pinfunction "C4_18") (pintype "passive"))
    )
    (net (code "53") (name "Net-(D10-A)") (class "Default")
      (node (ref "C31") (pin "2") (pinfunction "2_2") (pintype "passive"))
      (node (ref "C34") (pin "1") (pinfunction "1_1") (pintype "passive"))
      (node (ref "D10") (pin "1") (pinfunction "A_1") (pintype "passive"))
      (node (ref "D11") (pin "2") (pinfunction "K_2") (pintype "passive"))
      (node (ref "R37") (pin "2") (pinfunction "2_2") (pintype "passive"))
      (node (ref "U2") (pin "22") (pinfunction "C2_22") (pintype "passive"))
    )
    (net (code "54") (name "Net-(D10-K)") (class "Default")
      (node (ref "C29") (pin "2") (pinfunction "2_2") (pintype "passive"))
      (node (ref "C32") (pin "1") (pinfunction "1_1") (pintype "passive"))
      (node (ref "D10") (pin "2") (pinfunction "K_2") (pintype "passive"))
      (node (ref "D9") (pin "1") (pinfunction "A_1") (pintype "passive"))
      (node (ref "R34") (pin "2") (pinfunction "2_2") (pintype "passive"))
      (node (ref "U2") (pin "20") (pinfunction "C3_20") (pintype "passive"))
    )
    (net (code "55") (name "Net-(D11-A)") (class "Default")
      (node (ref "C33") (pin "2") (pinfunction "2_2") (pintype "passive"))
      (node (ref "C36") (pin "1") (pinfunction "1_1") (pintype "passive"))
      (node (ref "D11") (pin "1") (pinfunction "A_1") (pintype "passive"))
      (node (ref "D12") (pin "2") (pinfunction "K_2") (pintype "passive"))
      (node (ref "R40") (pin "2") (pinfunction "2_2") (pintype "passive"))
      (node (ref "U2") (pin "24") (pinfunction "C1_24") (pintype "passive"))
    )
    (net (code "56") (name "Net-(Q1-D)") (class "Default")
      (node (ref "Q1") (pin "1") (pinfunction "D_1") (pintype "passive"))
      (node (ref "R5") (pin "2") (pinfunction "2_2") (pintype "passive"))
    )
    (net (code "57") (name "Net-(Q1-G)") (class "Default")
      (node (ref "Q1") (pin "2") (pinfunction "G_2") (pintype "passive"))
      (node (ref "R4") (pin "1") (pinfunction "1_1") (pintype "passive"))
    )
    (net (code "58") (name "Net-(Q1-S)") (class "Default")
      (node (ref "F1") (pin "2") (pinfunction "2_2") (pintype "passive"))
      (node (ref "Q1") (pin "3") (pinfunction "S_3") (pintype "passive"))
      (node (ref "R1") (pin "1") (pinfunction "1_1") (pintype "passive"))
      (node (ref "R2") (pin "1") (pinfunction "1_1") (pintype "passive"))
      (node (ref "R3") (pin "1") (pinfunction "1_1") (pintype "passive"))
    )
    (net (code "59") (name "Net-(Q2-D)") (class "Default")
      (node (ref "Q2") (pin "1") (pinfunction "D_1") (pintype "passive"))
      (node (ref "R9") (pin "2") (pinfunction "2_2") (pintype "passive"))
    )
    (net (code "60") (name "Net-(Q2-G)") (class "Default")
      (node (ref "Q2") (pin "2") (pinfunction "G_2") (pintype "passive"))
      (node (ref "R8") (pin "1") (pinfunction "1_1") (pintype "passive"))
    )
    (net (code "61") (name "Net-(Q2-S)") (class "Default")
      (node (ref "F2") (pin "2") (pinfunction "2_2") (pintype "passive"))
      (node (ref "Q2") (pin "3") (pinfunction "S_3") (pintype "passive"))
      (node (ref "R5") (pin "1") (pinfunction "1_1") (pintype "passive"))
      (node (ref "R6") (pin "1") (pinfunction "1_1") (pintype "passive"))
    )
    (net (code "62") (name "Net-(Q3-D)") (class "Default")
      (node (ref "Q3") (pin "1") (pinfunction "D_1") (pintype "passive"))
      (node (ref "R12") (pin "2") (pinfunction "2_2") (pintype "passive"))
    )
    (net (code "63") (name "Net-(Q3-G)") (class "Default")
      (node (ref "Q3") (pin "2") (pinfunction "G_2") (pintype "passive"))
      (node (ref "R11") (pin "1") (pinfunction "1_1") (pintype "passive"))
    )
    (net (code "64") (name "Net-(Q3-S)") (class "Default")
      (node (ref "F3") (pin "2") (pinfunction "2_2") (pintype "passive"))
      (node (ref "Q3") (pin "3") (pinfunction "S_3") (pintype "passive"))
      (node (ref "R10") (pin "1") (pinfunction "1_1") (pintype "passive"))
      (node (ref "R9") (pin "1") (pinfunction "1_1") (pintype "passive"))
    )
    (net (code "65") (name "Net-(Q4-D)") (class "Default")
      (node (ref "Q4") (pin "1") (pinfunction "D_1") (pintype "passive"))
      (node (ref "R18") (pin "2") (pinfunction "2_2") (pintype "passive"))
    )
    (net (code "66") (name "Net-(Q4-G)") (class "Default")
      (node (ref "Q4") (pin "2") (pinfunction "G_2") (pintype "passive"))
      (node (ref "R17") (pin "1") (pinfunction "1_1") (pintype "passive"))
    )
    (net (code "67") (name "Net-(Q4-S)") (class "Default")
      (node (ref "F4") (pin "2") (pinfunction "2_2") (pintype "passive"))
      (node (ref "Q4") (pin "3") (pinfunction "S_3") (pintype "passive"))
      (node (ref "R12") (pin "1") (pinfunction "1_1") (pintype "passive"))
      (node (ref "R14") (pin "1") (pinfunction "1_1") (pintype "passive"))
    )
    (net (code "68") (name "Net-(Q5-B)") (class "Default")
      (node (ref "Q5") (pin "1") (pinfunction "B_1") (pintype "passive"))
      (node (ref "U2") (pin "38") (pinfunction "DRIVE_38") (pintype "passive"))
    )
    (net (code "69") (name "Net-(Q5-C)") (class "Default")
      (node (ref "C1") (pin "1") (pinfunction "1_1") (pintype "passive"))
      (node (ref "Q5") (pin "2") (pinfunction "C_2") (pintype "passive"))
      (node (ref "R1") (pin "2") (pinfunction "2_2") (pintype "passive"))
      (node (ref "U8") (pin "8") (pinfunction "IN_8") (pintype "passive"))
    )
    (net (code "70") (name "Net-(Q6-D)") (class "Default")
      (node (ref "Q6") (pin "1") (pinfunction "D_1") (pintype "passive"))
      (node (ref "R21") (pin "2") (pinfunction "2_2") (pintype "passive"))
    )
    (net (code "71") (name "Net-(Q6-G)") (class "Default")
      (node (ref "Q6") (pin "2") (pinfunction "G_2") (pintype "passive"))
      (node (ref "R20") (pin "1") (pinfunction "1_1") (pintype "passive"))
    )
    (net (code "72") (name "Net-(Q6-S)") (class "Default")
      (node (ref "F5") (pin "2") (pinfunction "2_2") (pintype "passive"))
      (node (ref "Q6") (pin "3") (pinfunction "S_3") (pintype "passive"))
      (node (ref "R18") (pin "1") (pinfunction "1_1") (pintype "passive"))
      (node (ref "R19") (pin "1") (pinfunction "1_1") (pintype "passive"))
    )
    (net (code "73") (name "Net-(Q7-D)") (class "Default")
      (node (ref "Q7") (pin "1") (pinfunction "D_1") (pintype "passive"))
      (node (ref "R24") (pin "2") (pinfunction "2_2") (pintype "passive"))
    )
    (net (code "74") (name "Net-(Q7-G)") (class "Default")
      (node (ref "Q7") (pin "2") (pinfunction "G_2") (pintype "passive"))
      (node (ref "R23") (pin "1") (pinfunction "1_1") (pintype "passive"))
    )
    (net (code "75") (name "Net-(Q7-S)") (class "Default")
      (node (ref "F6") (pin "2") (pinfunction "2_2") (pintype "passive"))
      (node (ref "Q7") (pin "3") (pinfunction "S_3") (pintype "passive"))
      (node (ref "R21") (pin "1") (pinfunction "1_1") (pintype "passive"))
      (node (ref "R22") (pin "1") (pinfunction "1_1") (pintype "passive"))
    )
    (net (code "76") (name "Net-(Q8-D)") (class "Default")
      (node (ref "Q8") (pin "1") (pinfunction "D_1") (pintype "passive"))
      (node (ref "R27") (pin "2") (pinfunction "2_2") (pintype "passive"))
    )
    (net (code "77") (name "Net-(Q8-G)") (class "Default")
      (node (ref "Q8") (pin "2") (pinfunction "G_2") (pintype "passive"))
      (node (ref "R26") (pin "1") (pinfunction "1_1") (pintype "passive"))
    )
    (net (code "78") (name "Net-(Q8-S)") (class "Default")
      (node (ref "F7") (pin "2") (pinfunction "2_2") (pintype "passive"))
      (node (ref "Q8") (pin "3") (pinfunction "S_3") (pintype "passive"))
      (node (ref "R24") (pin "1") (pinfunction "1_1") (pintype "passive"))
      (node (ref "R25") (pin "1") (pinfunction "1_1") (pintype "passive"))
    )
    (net (code "79") (name "Net-(Q9-D)") (class "Default")
      (node (ref "Q9") (pin "1") (pinfunction "D_1") (pintype "passive"))
      (node (ref "R30") (pin "2") (pinfunction "2_2") (pintype "passive"))
    )
    (net (code "80") (name "Net-(Q9-G)") (class "Default")
      (node (ref "Q9") (pin "2") (pinfunction "G_2") (pintype "passive"))
      (node (ref "R29") (pin "1") (pinfunction "1_1") (pintype "passive"))
    )
    (net (code "81") (name "Net-(Q9-S)") (class "Default")
      (node (ref "F8") (pin "2") (pinfunction "2_2") (pintype "passive"))
      (node (ref "Q9") (pin "3") (pinfunction "S_3") (pintype "passive"))
      (node (ref "R27") (pin "1") (pinfunction "1_1") (pintype "passive"))
      (node (ref "R28") (pin "1") (pinfunction "1_1") (pintype "passive"))
    )
    (net (code "82") (name "Net-(Q10-D)") (class "Default")
      (node (ref "Q10") (pin "1") (pinfunction "D_1") (pintype "passive"))
      (node (ref "R33") (pin "2") (pinfunction "2_2") (pintype "passive"))
    )
    (net (code "83") (name "Net-(Q10-G)") (class "Default")
      (node (ref "Q10") (pin "2") (pinfunction "G_2") (pintype "passive"))
      (node (ref "R32") (pin "1") (pinfunction "1_1") (pintype "passive"))
    )
    (net (code "84") (name "Net-(Q10-S)") (class "Default")
      (node (ref "F9") (pin "2") (pinfunction "2_2") (pintype "passive"))
      (node (ref "Q10") (pin "3") (pinfunction "S_3") (pintype "passive"))
      (node (ref "R30") (pin "1") (pinfunction "1_1") (pintype "passive"))
      (node (ref "R31") (pin "1") (pinfunction "1_1") (pintype "passive"))
    )
    (net (code "85") (name "Net-(Q11-D)") (class "Default")
      (node (ref "Q11") (pin "1") (pinfunction "D_1") (pintype "passive"))
      (node (ref "R36") (pin "2") (pinfunction "2_2") (pintype "passive"))
    )
    (net (code "86") (name "Net-(Q11-G)") (class "Default")
      (node (ref "Q11") (pin "2") (pinfunction "G_2") (pintype "passive"))
      (node (ref "R35") (pin "1") (pinfunction "1_1") (pintype "passive"))
    )
    (net (code "87") (name "Net-(Q11-S)") (class "Default")
      (node (ref "F10") (pin "2") (pinfunction "2_2") (pintype "passive"))
      (node (ref "Q11") (pin "3") (pinfunction "S_3") (pintype "passive"))
      (node (ref "R33") (pin "1") (pinfunction "1_1") (pintype "passive"))
      (node (ref "R34") (pin "1") (pinfunction "1_1") (pintype "passive"))
    )
    (net (code "88") (name "Net-(Q12-D)") (class "Default")
      (node (ref "Q12") (pin "1") (pinfunction "D_1") (pintype "passive"))
      (node (ref "R39") (pin "2") (pinfunction "2_2") (pintype "passive"))
    )
    (net (code "89") (name "Net-(Q12-G)") (class "Default")
      (node (ref "Q12") (pin "2") (pinfunction "G_2") (pintype "passive"))
      (node (ref "R38") (pin "1") (pinfunction "1_1") (pintype "passive"))
    )
    (net (code "90") (name "Net-(Q12-S)") (class "Default")
      (node (ref "F11") (pin "2") (pinfunction "2_2") (pintype "passive"))
      (node (ref "Q12") (pin "3") (pinfunction "S_3") (pintype "passive"))
      (node (ref "R36") (pin "1") (pinfunction "1_1") (pintype "passive"))
      (node (ref "R37") (pin "1") (pinfunction "1_1") (pintype "passive"))
    )
    (net (code "91") (name "Net-(Q13-D)") (class "Default")
      (node (ref "Q13") (pin "1") (pinfunction "D_1") (pintype "passive"))
      (node (ref "R42") (pin "2") (pinfunction "2_2") (pintype "passive"))
    )
    (net (code "92") (name "Net-(Q13-G)") (class "Default")
      (node (ref "Q13") (pin "2") (pinfunction "G_2") (pintype "passive"))
      (node (ref "R41") (pin "1") (pinfunction "1_1") (pintype "passive"))
    )
    (net (code "93") (name "Net-(Q13-S)") (class "Default")
      (node (ref "F12") (pin "2") (pinfunction "2_2") (pintype "passive"))
      (node (ref "Q13") (pin "3") (pinfunction "S_3") (pintype "passive"))
      (node (ref "R39") (pin "1") (pinfunction "1_1") (pintype "passive"))
      (node (ref "R40") (pin "1") (pinfunction "1_1") (pintype "passive"))
    )
    (net (code "94") (name "Net-(U2-IBIAS)") (class "Default")
      (node (ref "R15") (pin "1") (pinfunction "1_1") (pintype "passive"))
      (node (ref "U2") (pin "45") (pinfunction "IBIAS_45") (pintype "passive"))
    )
    (net (code "95") (name "Net-(U2-ICMP)") (class "Default")
      (node (ref "R15") (pin "2") (pinfunction "2_2") (pintype "passive"))
      (node (ref "R16") (pin "1") (pinfunction "1_1") (pintype "passive"))
      (node (ref "U2") (pin "46") (pinfunction "ICMP_46") (pintype "passive"))
    )
    (net (code "96") (name "Net-(U2-S1)") (class "Default")
      (node (ref "R41") (pin "2") (pinfunction "2_2") (pintype "passive"))
      (node (ref "U2") (pin "25") (pinfunction "S1_25") (pintype "passive"))
    )
    (net (code "97") (name "Net-(U2-S2)") (class "Default")
      (node (ref "R38") (pin "2") (pinfunction "2_2") (pintype "passive"))
      (node (ref "U2") (pin "23") (pinfunction "S2_23") (pintype "passive"))
    )
    (net (code "98") (name "Net-(U2-S3)") (class "Default")
      (node (ref "R35") (pin "2") (pinfunction "2_2") (pintype "passive"))
      (node (ref "U2") (pin "21") (pinfunction "S3_21") (pintype "passive"))
    )
    (net (code "99") (name "Net-(U2-S4)") (class "Default")
      (node (ref "R32") (pin "2") (pinfunction "2_2") (pintype "passive"))
      (node (ref "U2") (pin "19") (pinfunction "S4_19") (pintype "passive"))
    )
    (net (code "100") (name "Net-(U2-S5)") (class "Default")
      (node (ref "R29") (pin "2") (pinfunction "2_2") (pintype "passive"))
      (node (ref "U2") (pin "17") (pinfunction "S5_17") (pintype "passive"))
    )
    (net (code "101") (name "Net-(U2-S6)") (class "Default")
      (node (ref "R26") (pin "2") (pinfunction "2_2") (pintype "passive"))
      (node (ref "U2") (pin "15") (pinfunction "S6_15") (pintype "passive"))
    )
    (net (code "102") (name "Net-(U2-S7)") (class "Default")
      (node (ref "R23") (pin "2") (pinfunction "2_2") (pintype "passive"))
      (node (ref "U2") (pin "13") (pinfunction "S7_13") (pintype "passive"))
    )
    (net (code "103") (name "Net-(U2-S8)") (class "Default")
      (node (ref "R20") (pin "2") (pinfunction "2_2") (pintype "passive"))
      (node (ref "U2") (pin "11") (pinfunction "S8_11") (pintype "passive"))
    )
    (net (code "104") (name "Net-(U2-S9)") (class "Default")
      (node (ref "R17") (pin "2") (pinfunction "2_2") (pintype "passive"))
      (node (ref "U2") (pin "9") (pinfunction "S9_9") (pintype "passive"))
    )
    (net (code "105") (name "Net-(U2-S10)") (class "Default")
      (node (ref "R11") (pin "2") (pinfunction "2_2") (pintype "passive"))
      (node (ref "U2") (pin "7") (pinfunction "S10_7") (pintype "passive"))
    )
    (net (code "106") (name "Net-(U2-S11)") (class "Default")
      (node (ref "R8") (pin "2") (pinfunction "2_2") (pintype "passive"))
      (node (ref "U2") (pin "5") (pinfunction "S11_5") (pintype "passive"))
    )
    (net (code "107") (name "Net-(U2-S12)") (class "Default")
      (node (ref "R4") (pin "2") (pinfunction "2_2") (pintype "passive"))
      (node (ref "U2") (pin "3") (pinfunction "S12_3") (pintype "passive"))
    )
    (net (code "108") (name "Net-(U2-V+)") (class "Default")
      (node (ref "R2") (pin "2") (pinfunction "2_2") (pintype "passive"))
      (node (ref "U2") (pin "1") (pinfunction "V+_1") (pintype "passive"))
    )
    (net (code "109") (name "Net-(U2-VREF1)") (class "Default")
      (node (ref "C18") (pin "1") (pinfunction "1_1") (pintype "passive"))
      (node (ref "U2") (pin "35") (pinfunction "VREF1_35") (pintype "passive"))
    )
    (net (code "110") (name "Net-(U2-VREF2)") (class "Default")
      (node (ref "C17") (pin "1") (pinfunction "1_1") (pintype "passive"))
      (node (ref "U2") (pin "34") (pinfunction "VREF2_34") (pintype "passive"))
    )
    (net (code "111") (name "TS-") (class "Default")
      (node (ref "C13") (pin "2") (pinfunction "2_2") (pintype "passive"))
      (node (ref "C14") (pin "2") (pinfunction "2_2") (pintype "passive"))
      (node (ref "C2") (pin "2") (pinfunction "2_2") (pintype "passive"))
      (node (ref "C20") (pin "2") (pinfunction "2_2") (pintype "passive"))
      (node (ref "C21") (pin "2") (pinfunction "2_2") (pintype "passive"))
      (node (ref "C22") (pin "2") (pinfunction "2_2") (pintype "passive"))
      (node (ref "C35") (pin "2") (pinfunction "2_2") (pintype "passive"))
      (node (ref "D12") (pin "1") (pinfunction "A_1") (pintype "passive"))
      (node (ref "R16") (pin "2") (pinfunction "2_2") (pintype "passive"))
      (node (ref "R42") (pin "1") (pinfunction "1_1") (pintype "passive"))
      (node (ref "U2") (pin "26") (pinfunction "C0_26") (pintype "passive"))
      (node (ref "U2") (pin "30") (pinfunction "V-_30") (pintype "passive"))
      (node (ref "U2") (pin "31") (pinfunction "V-_31") (pintype "passive"))
      (node (ref "U2") (pin "36") (pinfunction "DTEN_36") (pintype "passive"))
      (node (ref "U2") (pin "40") (pinfunction "ISOMD_40") (pintype "passive"))
      (node (ref "U8") (pin "2") (pinfunction "GND_2") (pintype "passive"))
      (node (ref "U8") (pin "3") (pinfunction "GND_3") (pintype "passive"))
      (node (ref "U8") (pin "6") (pinfunction "GND_6") (pintype "passive"))
      (node (ref "U8") (pin "7") (pinfunction "GND_7") (pintype "passive"))
    )
    (net (code "112") (name "unconnected-(U1-GND-Pad10)") (class "Default")
      (node (ref "U1") (pin "10") (pinfunction "GND_10") (pintype "passive"))
    )
    (net (code "113") (name "unconnected-(U1-IMA-Pad8)") (class "Default")
      (node (ref "U1") (pin "8") (pinfunction "IMA_8") (pintype "passive"))
    )
    (net (code "114") (name "unconnected-(U1-IMA-Pad9)") (class "Default")
      (node (ref "U1") (pin "9") (pinfunction "IMA_9") (pintype "passive"))
    )
    (net (code "115") (name "unconnected-(U1-IPA-Pad6)") (class "Default")
      (node (ref "U1") (pin "6") (pinfunction "IPA_6") (pintype "passive"))
    )
    (net (code "116") (name "unconnected-(U1-IPA-Pad11)") (class "Default")
      (node (ref "U1") (pin "11") (pinfunction "IPA_11") (pintype "passive"))
    )
    (net (code "117") (name "unconnected-(U1-NC-Pad4)") (class "Default")
      (node (ref "U1") (pin "4") (pinfunction "NC_4") (pintype "passive"))
    )
    (net (code "118") (name "unconnected-(U1-NC-Pad5)") (class "Default")
      (node (ref "U1") (pin "5") (pinfunction "NC_5") (pintype "passive"))
    )
    (net (code "119") (name "unconnected-(U1-NC-Pad12)") (class "Default")
      (node (ref "U1") (pin "12") (pinfunction "NC_12") (pintype "passive"))
    )
    (net (code "120") (name "unconnected-(U1-NC-Pad13)") (class "Default")
      (node (ref "U1") (pin "13") (pinfunction "NC_13") (pintype "passive"))
    )
    (net (code "121") (name "unconnected-(U1-NC-Pad15)") (class "Default")
      (node (ref "U1") (pin "15") (pinfunction "NC_15") (pintype "passive"))
    )
    (net (code "122") (name "unconnected-(U2-GPIO1-Pad27)") (class "Default")
      (node (ref "U2") (pin "27") (pinfunction "GPIO1_27") (pintype "passive"))
    )
    (net (code "123") (name "unconnected-(U2-GPIO2-Pad28)") (class "Default")
      (node (ref "U2") (pin "28") (pinfunction "GPIO2_28") (pintype "passive"))
    )
    (net (code "124") (name "unconnected-(U2-GPIO3-Pad29)") (class "Default")
      (node (ref "U2") (pin "29") (pinfunction "GPIO3_29") (pintype "passive"))
    )
    (net (code "125") (name "unconnected-(U2-GPIO4-Pad32)") (class "Default")
      (node (ref "U2") (pin "32") (pinfunction "GPIO4_32") (pintype "passive"))
    )
    (net (code "126") (name "unconnected-(U2-GPIO5-Pad33)") (class "Default")
      (node (ref "U2") (pin "33") (pinfunction "GPIO5_33") (pintype "passive"))
    )
    (net (code "127") (name "unconnected-(U2-WDT-Pad39)") (class "Default")
      (node (ref "U2") (pin "39") (pinfunction "WDT_39") (pintype "passive"))
    )
    (net (code "128") (name "unconnected-(U8-NC-Pad4)") (class "Default")
      (node (ref "U8") (pin "4") (pinfunction "NC_4") (pintype "passive"))
    )
    (net (code "129") (name "unconnected-(U8-NC-Pad5)") (class "Default")
      (node (ref "U8") (pin "5") (pinfunction "NC_5") (pintype "passive"))
    )
  )
)
